# LM35.net
KiCad netlist of a schematic drawn in Altium Designer
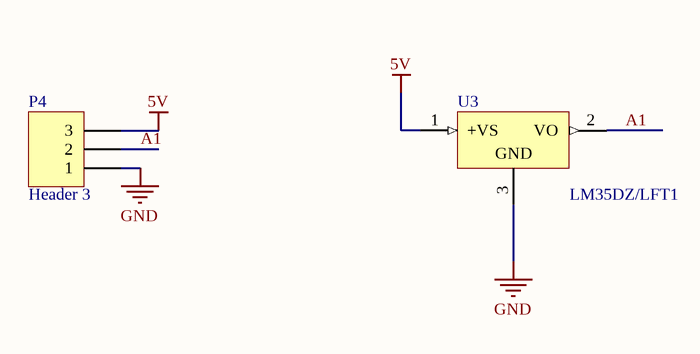
[diagram p0: LM35.SchDoc]

(export (version "E")
  (design (tool "Eeschema 10.0.6"))
  (components
    (comp (ref "P4")
      (value "Header 3")
      (footprint "HDR1X3")
      (description "Header, 3-Pin")
      (fields (field (name "PUBLISHER") "Altium Limited"))
      (libsource (lib "Miscellaneous Connectors") (part "Header 3"))
    )
    (comp (ref "U3")
      (value "LM35DZ/LFT1")
      (footprint "Z03A")
      (description "IC SENSOR PREC CENT TEMP TO92-3")
      (fields (field (name "MANUFACTURER") "Texas Instruments"))
      (libsource (lib "General") (part "LM35DZ/LFT1"))
    )
  )
  (nets
    (net (code "1") (name "/A1") (class "Default")
      (node (ref "P4") (pin "2") (pinfunction "2_2") (pintype "passive"))
      (node (ref "U3") (pin "2") (pinfunction "VO_2") (pintype "output"))
    )
    (net (code "2") (name "5V") (class "Default")
      (node (ref "P4") (pin "3") (pinfunction "3_3") (pintype "passive"))
      (node (ref "U3") (pin "1") (pinfunction "+VS_1") (pintype "input"))
    )
    (net (code "3") (name "GND") (class "Default")
      (node (ref "P4") (pin "1") (pinfunction "1_1") (pintype "passive"))
      (node (ref "U3") (pin "3") (pinfunction "GND_3") (pintype "power_in"))
    )
  )
)
